# MAT_CABLING_CONNECTOR.net
KiCad netlist of a schematic drawn in Altium Designer
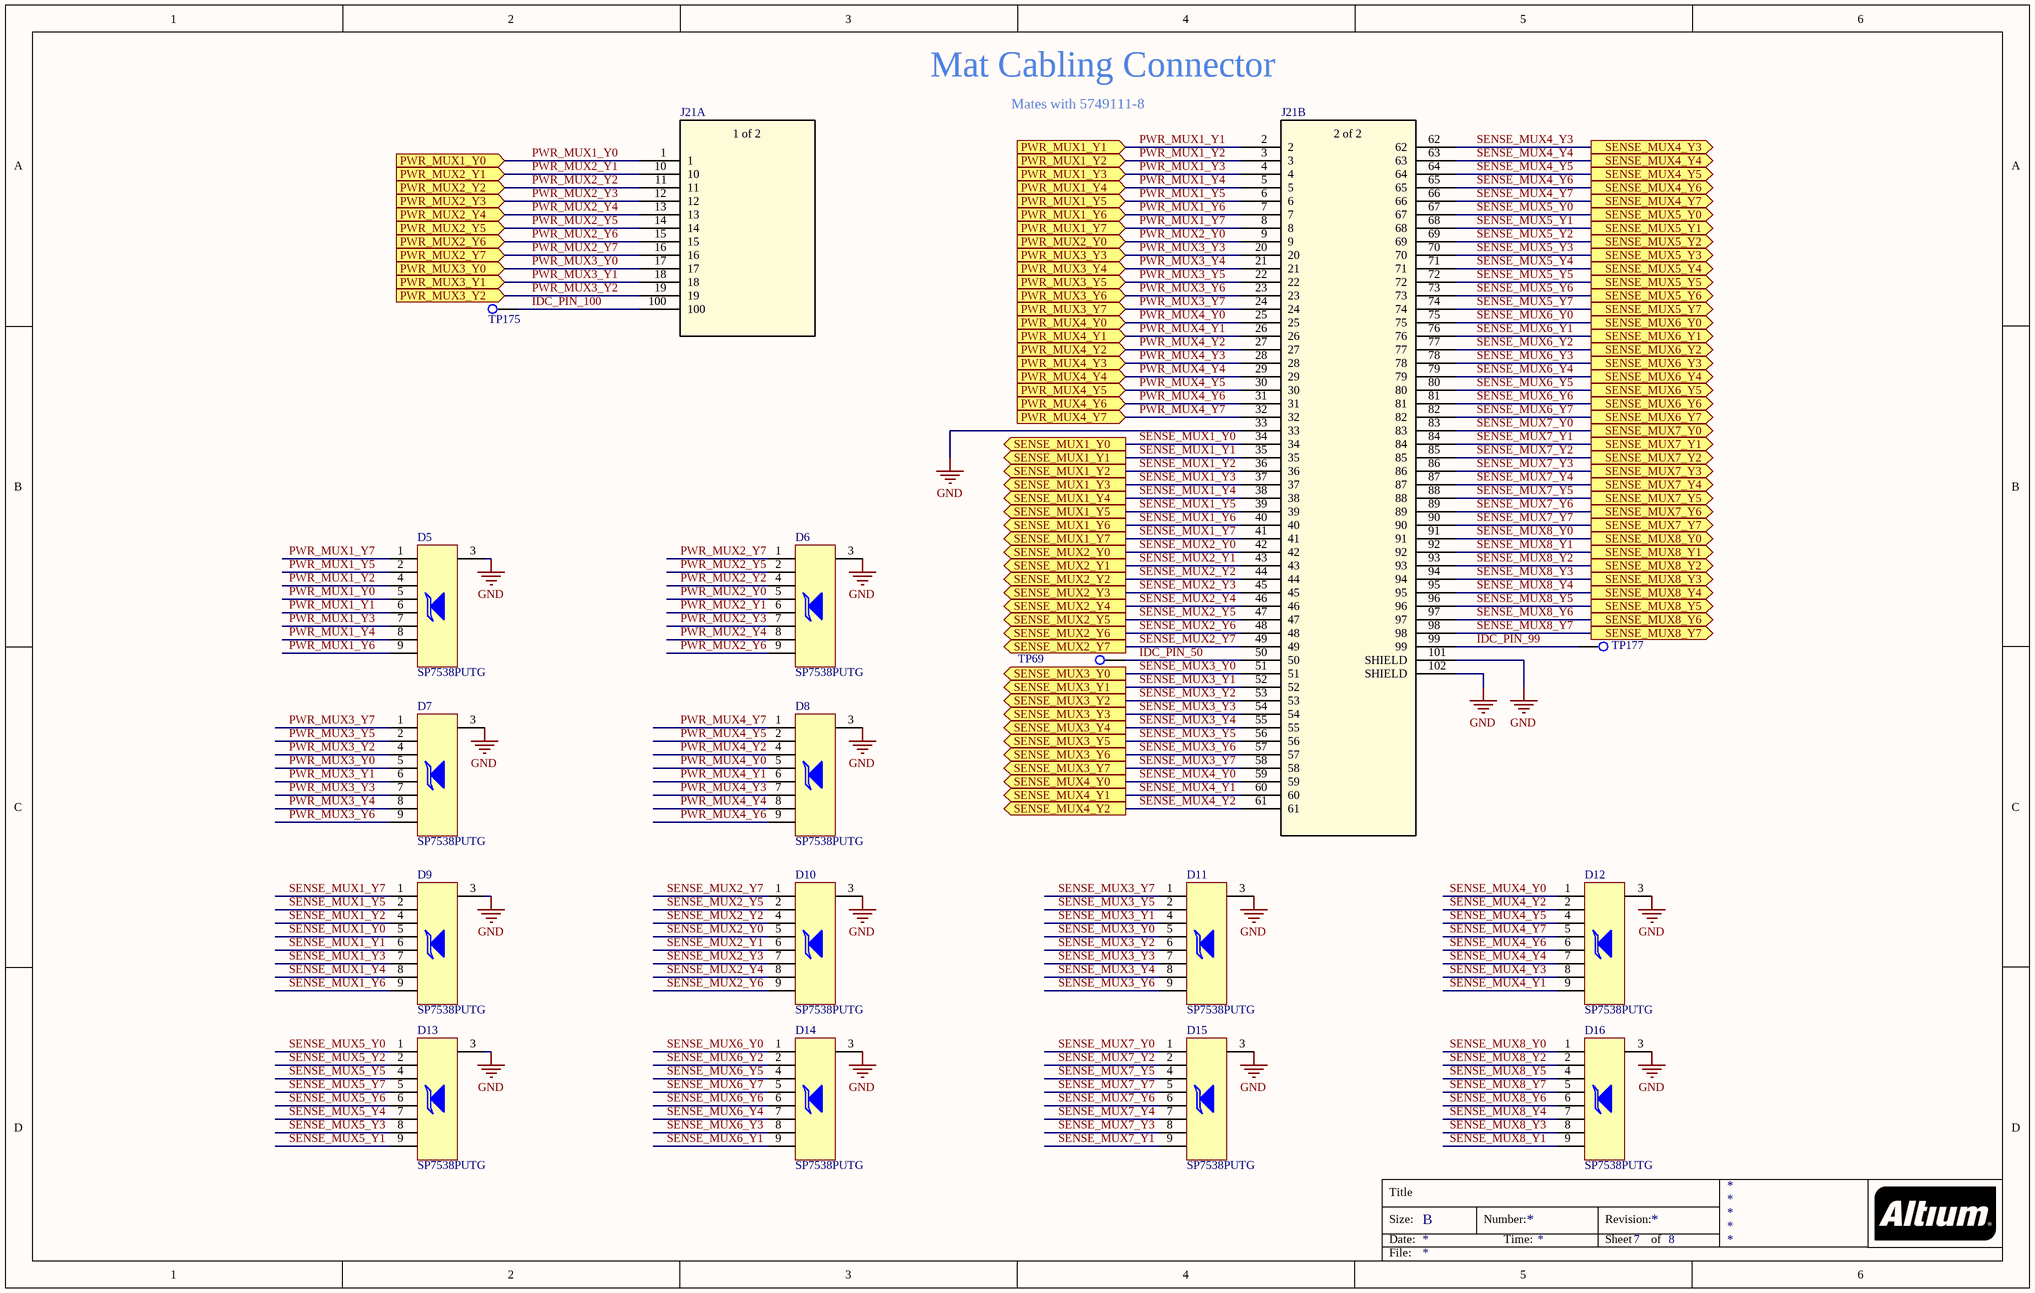
[diagram p0: MAT_CABLING_CONNECTOR.SchDoc]

(export (version "E")
  (design (tool "Eeschema 10.0.6"))
  (components
    (comp (ref "D5")
      (value "SP7538PUTG")
      (footprint "SP7538PUTG")
      (description "ESD Suppressor TVS Octal Uni-Dir 25kV 9-Pin UDFN T/R")
      (fields
        (field (name "MANUFACTURER") "Littelfuse")
        (field (name "MANUFACTURER PART NUMBER") "SP7538PUTG")
      )
      (libsource (lib "MLBSchLib") (part "SP7538PUTG"))
    )
    (comp (ref "D6")
      (value "SP7538PUTG")
      (footprint "SP7538PUTG")
      (description "ESD Suppressor TVS Octal Uni-Dir 25kV 9-Pin UDFN T/R")
      (fields
        (field (name "MANUFACTURER") "Littelfuse")
        (field (name "MANUFACTURER PART NUMBER") "SP7538PUTG")
      )
      (libsource (lib "MLBSchLib") (part "SP7538PUTG"))
    )
    (comp (ref "D7")
      (value "SP7538PUTG")
      (footprint "SP7538PUTG")
      (description "ESD Suppressor TVS Octal Uni-Dir 25kV 9-Pin UDFN T/R")
      (fields
        (field (name "MANUFACTURER") "Littelfuse")
        (field (name "MANUFACTURER PART NUMBER") "SP7538PUTG")
      )
      (libsource (lib "MLBSchLib") (part "SP7538PUTG"))
    )
    (comp (ref "D8")
      (value "SP7538PUTG")
      (footprint "SP7538PUTG")
      (description "ESD Suppressor TVS Octal Uni-Dir 25kV 9-Pin UDFN T/R")
      (fields
        (field (name "MANUFACTURER") "Littelfuse")
        (field (name "MANUFACTURER PART NUMBER") "SP7538PUTG")
      )
      (libsource (lib "MLBSchLib") (part "SP7538PUTG"))
    )
    (comp (ref "D9")
      (value "SP7538PUTG")
      (footprint "SP7538PUTG")
      (description "ESD Suppressor TVS Octal Uni-Dir 25kV 9-Pin UDFN T/R")
      (fields
        (field (name "MANUFACTURER") "Littelfuse")
        (field (name "MANUFACTURER PART NUMBER") "SP7538PUTG")
      )
      (libsource (lib "MLBSchLib") (part "SP7538PUTG"))
    )
    (comp (ref "D10")
      (value "SP7538PUTG")
      (footprint "SP7538PUTG")
      (description "ESD Suppressor TVS Octal Uni-Dir 25kV 9-Pin UDFN T/R")
      (fields
        (field (name "MANUFACTURER") "Littelfuse")
        (field (name "MANUFACTURER PART NUMBER") "SP7538PUTG")
      )
      (libsource (lib "MLBSchLib") (part "SP7538PUTG"))
    )
    (comp (ref "D11")
      (value "SP7538PUTG")
      (footprint "SP7538PUTG")
      (description "ESD Suppressor TVS Octal Uni-Dir 25kV 9-Pin UDFN T/R")
      (fields
        (field (name "MANUFACTURER") "Littelfuse")
        (field (name "MANUFACTURER PART NUMBER") "SP7538PUTG")
      )
      (libsource (lib "MLBSchLib") (part "SP7538PUTG"))
    )
    (comp (ref "D12")
      (value "SP7538PUTG")
      (footprint "SP7538PUTG")
      (description "ESD Suppressor TVS Octal Uni-Dir 25kV 9-Pin UDFN T/R")
      (fields
        (field (name "MANUFACTURER") "Littelfuse")
        (field (name "MANUFACTURER PART NUMBER") "SP7538PUTG")
      )
      (libsource (lib "MLBSchLib") (part "SP7538PUTG"))
    )
    (comp (ref "D13")
      (value "SP7538PUTG")
      (footprint "SP7538PUTG")
      (description "ESD Suppressor TVS Octal Uni-Dir 25kV 9-Pin UDFN T/R")
      (fields
        (field (name "MANUFACTURER") "Littelfuse")
        (field (name "MANUFACTURER PART NUMBER") "SP7538PUTG")
      )
      (libsource (lib "MLBSchLib") (part "SP7538PUTG"))
    )
    (comp (ref "D14")
      (value "SP7538PUTG")
      (footprint "SP7538PUTG")
      (description "ESD Suppressor TVS Octal Uni-Dir 25kV 9-Pin UDFN T/R")
      (fields
        (field (name "MANUFACTURER") "Littelfuse")
        (field (name "MANUFACTURER PART NUMBER") "SP7538PUTG")
      )
      (libsource (lib "MLBSchLib") (part "SP7538PUTG"))
    )
    (comp (ref "D15")
      (value "SP7538PUTG")
      (footprint "SP7538PUTG")
      (description "ESD Suppressor TVS Octal Uni-Dir 25kV 9-Pin UDFN T/R")
      (fields
        (field (name "MANUFACTURER") "Littelfuse")
        (field (name "MANUFACTURER PART NUMBER") "SP7538PUTG")
      )
      (libsource (lib "MLBSchLib") (part "SP7538PUTG"))
    )
    (comp (ref "D16")
      (value "SP7538PUTG")
      (footprint "SP7538PUTG")
      (description "ESD Suppressor TVS Octal Uni-Dir 25kV 9-Pin UDFN T/R")
      (fields
        (field (name "MANUFACTURER") "Littelfuse")
        (field (name "MANUFACTURER PART NUMBER") "SP7538PUTG")
      )
      (libsource (lib "MLBSchLib") (part "SP7538PUTG"))
    )
    (comp (ref "J21")
      (value "1-787082-8")
      (footprint "CONN100_1-787082-8_TEC")
      (description "No Description Available")
      (fields
        (field (name "MANUFACTURER") "TE Connectivity AMP Connectors")
        (field (name "COPYRIGHT") "Copyright (C) 2022 Ultra Librarian. All rights reserved.")
      )
      (libsource (lib "") (part "1-787082-8_1"))
    )
    (comp (ref "TP69")
      (value "RCU-0C")
      (footprint "TP+195X110")
      (description "Natural PC Test Point , Plating Surface Mount Mounting Type")
      (fields (field (name "MANUFACTURER") "TE Connectivity AMP Connectors"))
      (libsource (lib "MLBSchLib") (part "RCU-0C"))
    )
    (comp (ref "TP175")
      (value "RCU-0C")
      (footprint "TP+195X110")
      (description "Natural PC Test Point , Plating Surface Mount Mounting Type")
      (fields (field (name "MANUFACTURER") "TE Connectivity AMP Connectors"))
      (libsource (lib "MLBSchLib") (part "RCU-0C"))
    )
    (comp (ref "TP177")
      (value "RCU-0C")
      (footprint "TP+195X110")
      (description "Natural PC Test Point , Plating Surface Mount Mounting Type")
      (fields (field (name "MANUFACTURER") "TE Connectivity AMP Connectors"))
      (libsource (lib "MLBSchLib") (part "RCU-0C"))
    )
  )
  (nets
    (net (code "1") (name "/IDC_PIN_50") (class "Default")
      (node (ref "J21") (pin "50") (pinfunction "50_50") (pintype "passive"))
      (node (ref "TP69") (pin "1") (pinfunction "1_1") (pintype "passive"))
    )
    (net (code "2") (name "/IDC_PIN_99") (class "Default")
      (node (ref "J21") (pin "99") (pinfunction "99_99") (pintype "passive"))
      (node (ref "TP177") (pin "1") (pinfunction "1_1") (pintype "passive"))
    )
    (net (code "3") (name "/IDC_PIN_100") (class "Default")
      (node (ref "J21") (pin "100") (pinfunction "100_100") (pintype "passive"))
      (node (ref "TP175") (pin "1") (pinfunction "1_1") (pintype "passive"))
    )
    (net (code "4") (name "/PWR_MUX1_Y0") (class "Default")
      (node (ref "D5") (pin "5") (pinfunction "5_5") (pintype "passive"))
      (node (ref "J21") (pin "1") (pinfunction "1_1") (pintype "passive"))
    )
    (net (code "5") (name "/PWR_MUX1_Y1") (class "Default")
      (node (ref "D5") (pin "6") (pinfunction "6_6") (pintype "passive"))
      (node (ref "J21") (pin "2") (pinfunction "2_2") (pintype "passive"))
    )
    (net (code "6") (name "/PWR_MUX1_Y2") (class "Default")
      (node (ref "D5") (pin "4") (pinfunction "4_4") (pintype "passive"))
      (node (ref "J21") (pin "3") (pinfunction "3_3") (pintype "passive"))
    )
    (net (code "7") (name "/PWR_MUX1_Y3") (class "Default")
      (node (ref "D5") (pin "7") (pinfunction "7_7") (pintype "passive"))
      (node (ref "J21") (pin "4") (pinfunction "4_4") (pintype "passive"))
    )
    (net (code "8") (name "/PWR_MUX1_Y4") (class "Default")
      (node (ref "D5") (pin "8") (pinfunction "8_8") (pintype "passive"))
      (node (ref "J21") (pin "5") (pinfunction "5_5") (pintype "passive"))
    )
    (net (code "9") (name "/PWR_MUX1_Y5") (class "Default")
      (node (ref "D5") (pin "2") (pinfunction "2_2") (pintype "passive"))
      (node (ref "J21") (pin "6") (pinfunction "6_6") (pintype "passive"))
    )
    (net (code "10") (name "/PWR_MUX1_Y6") (class "Default")
      (node (ref "D5") (pin "9") (pinfunction "9_9") (pintype "passive"))
      (node (ref "J21") (pin "7") (pinfunction "7_7") (pintype "passive"))
    )
    (net (code "11") (name "/PWR_MUX1_Y7") (class "Default")
      (node (ref "D5") (pin "1") (pinfunction "1_1") (pintype "passive"))
      (node (ref "J21") (pin "8") (pinfunction "8_8") (pintype "passive"))
    )
    (net (code "12") (name "/PWR_MUX2_Y0") (class "Default")
      (node (ref "D6") (pin "5") (pinfunction "5_5") (pintype "passive"))
      (node (ref "J21") (pin "9") (pinfunction "9_9") (pintype "passive"))
    )
    (net (code "13") (name "/PWR_MUX2_Y1") (class "Default")
      (node (ref "D6") (pin "6") (pinfunction "6_6") (pintype "passive"))
      (node (ref "J21") (pin "10") (pinfunction "10_10") (pintype "passive"))
    )
    (net (code "14") (name "/PWR_MUX2_Y2") (class "Default")
      (node (ref "D6") (pin "4") (pinfunction "4_4") (pintype "passive"))
      (node (ref "J21") (pin "11") (pinfunction "11_11") (pintype "passive"))
    )
    (net (code "15") (name "/PWR_MUX2_Y3") (class "Default")
      (node (ref "D6") (pin "7") (pinfunction "7_7") (pintype "passive"))
      (node (ref "J21") (pin "12") (pinfunction "12_12") (pintype "passive"))
    )
    (net (code "16") (name "/PWR_MUX2_Y4") (class "Default")
      (node (ref "D6") (pin "8") (pinfunction "8_8") (pintype "passive"))
      (node (ref "J21") (pin "13") (pinfunction "13_13") (pintype "passive"))
    )
    (net (code "17") (name "/PWR_MUX2_Y5") (class "Default")
      (node (ref "D6") (pin "2") (pinfunction "2_2") (pintype "passive"))
      (node (ref "J21") (pin "14") (pinfunction "14_14") (pintype "passive"))
    )
    (net (code "18") (name "/PWR_MUX2_Y6") (class "Default")
      (node (ref "D6") (pin "9") (pinfunction "9_9") (pintype "passive"))
      (node (ref "J21") (pin "15") (pinfunction "15_15") (pintype "passive"))
    )
    (net (code "19") (name "/PWR_MUX2_Y7") (class "Default")
      (node (ref "D6") (pin "1") (pinfunction "1_1") (pintype "passive"))
      (node (ref "J21") (pin "16") (pinfunction "16_16") (pintype "passive"))
    )
    (net (code "20") (name "/PWR_MUX3_Y0") (class "Default")
      (node (ref "D7") (pin "5") (pinfunction "5_5") (pintype "passive"))
      (node (ref "J21") (pin "17") (pinfunction "17_17") (pintype "passive"))
    )
    (net (code "21") (name "/PWR_MUX3_Y1") (class "Default")
      (node (ref "D7") (pin "6") (pinfunction "6_6") (pintype "passive"))
      (node (ref "J21") (pin "18") (pinfunction "18_18") (pintype "passive"))
    )
    (net (code "22") (name "/PWR_MUX3_Y2") (class "Default")
      (node (ref "D7") (pin "4") (pinfunction "4_4") (pintype "passive"))
      (node (ref "J21") (pin "19") (pinfunction "19_19") (pintype "passive"))
    )
    (net (code "23") (name "/PWR_MUX3_Y3") (class "Default")
      (node (ref "D7") (pin "7") (pinfunction "7_7") (pintype "passive"))
      (node (ref "J21") (pin "20") (pinfunction "20_20") (pintype "passive"))
    )
    (net (code "24") (name "/PWR_MUX3_Y4") (class "Default")
      (node (ref "D7") (pin "8") (pinfunction "8_8") (pintype "passive"))
      (node (ref "J21") (pin "21") (pinfunction "21_21") (pintype "passive"))
    )
    (net (code "25") (name "/PWR_MUX3_Y5") (class "Default")
      (node (ref "D7") (pin "2") (pinfunction "2_2") (pintype "passive"))
      (node (ref "J21") (pin "22") (pinfunction "22_22") (pintype "passive"))
    )
    (net (code "26") (name "/PWR_MUX3_Y6") (class "Default")
      (node (ref "D7") (pin "9") (pinfunction "9_9") (pintype "passive"))
      (node (ref "J21") (pin "23") (pinfunction "23_23") (pintype "passive"))
    )
    (net (code "27") (name "/PWR_MUX3_Y7") (class "Default")
      (node (ref "D7") (pin "1") (pinfunction "1_1") (pintype "passive"))
      (node (ref "J21") (pin "24") (pinfunction "24_24") (pintype "passive"))
    )
    (net (code "28") (name "/PWR_MUX4_Y0") (class "Default")
      (node (ref "D8") (pin "5") (pinfunction "5_5") (pintype "passive"))
      (node (ref "J21") (pin "25") (pinfunction "25_25") (pintype "passive"))
    )
    (net (code "29") (name "/PWR_MUX4_Y1") (class "Default")
      (node (ref "D8") (pin "6") (pinfunction "6_6") (pintype "passive"))
      (node (ref "J21") (pin "26") (pinfunction "26_26") (pintype "passive"))
    )
    (net (code "30") (name "/PWR_MUX4_Y2") (class "Default")
      (node (ref "D8") (pin "4") (pinfunction "4_4") (pintype "passive"))
      (node (ref "J21") (pin "27") (pinfunction "27_27") (pintype "passive"))
    )
    (net (code "31") (name "/PWR_MUX4_Y3") (class "Default")
      (node (ref "D8") (pin "7") (pinfunction "7_7") (pintype "passive"))
      (node (ref "J21") (pin "28") (pinfunction "28_28") (pintype "passive"))
    )
    (net (code "32") (name "/PWR_MUX4_Y4") (class "Default")
      (node (ref "D8") (pin "8") (pinfunction "8_8") (pintype "passive"))
      (node (ref "J21") (pin "29") (pinfunction "29_29") (pintype "passive"))
    )
    (net (code "33") (name "/PWR_MUX4_Y5") (class "Default")
      (node (ref "D8") (pin "2") (pinfunction "2_2") (pintype "passive"))
      (node (ref "J21") (pin "30") (pinfunction "30_30") (pintype "passive"))
    )
    (net (code "34") (name "/PWR_MUX4_Y6") (class "Default")
      (node (ref "D8") (pin "9") (pinfunction "9_9") (pintype "passive"))
      (node (ref "J21") (pin "31") (pinfunction "31_31") (pintype "passive"))
    )
    (net (code "35") (name "/PWR_MUX4_Y7") (class "Default")
      (node (ref "D8") (pin "1") (pinfunction "1_1") (pintype "passive"))
      (node (ref "J21") (pin "32") (pinfunction "32_32") (pintype "passive"))
    )
    (net (code "36") (name "/SENSE_MUX1_Y0") (class "Default")
      (node (ref "D9") (pin "5") (pinfunction "5_5") (pintype "passive"))
      (node (ref "J21") (pin "34") (pinfunction "34_34") (pintype "passive"))
    )
    (net (code "37") (name "/SENSE_MUX1_Y1") (class "Default")
      (node (ref "D9") (pin "6") (pinfunction "6_6") (pintype "passive"))
      (node (ref "J21") (pin "35") (pinfunction "35_35") (pintype "passive"))
    )
    (net (code "38") (name "/SENSE_MUX1_Y2") (class "Default")
      (node (ref "D9") (pin "4") (pinfunction "4_4") (pintype "passive"))
      (node (ref "J21") (pin "36") (pinfunction "36_36") (pintype "passive"))
    )
    (net (code "39") (name "/SENSE_MUX1_Y3") (class "Default")
      (node (ref "D9") (pin "7") (pinfunction "7_7") (pintype "passive"))
      (node (ref "J21") (pin "37") (pinfunction "37_37") (pintype "passive"))
    )
    (net (code "40") (name "/SENSE_MUX1_Y4") (class "Default")
      (node (ref "D9") (pin "8") (pinfunction "8_8") (pintype "passive"))
      (node (ref "J21") (pin "38") (pinfunction "38_38") (pintype "passive"))
    )
    (net (code "41") (name "/SENSE_MUX1_Y5") (class "Default")
      (node (ref "D9") (pin "2") (pinfunction "2_2") (pintype "passive"))
      (node (ref "J21") (pin "39") (pinfunction "39_39") (pintype "passive"))
    )
    (net (code "42") (name "/SENSE_MUX1_Y6") (class "Default")
      (node (ref "D9") (pin "9") (pinfunction "9_9") (pintype "passive"))
      (node (ref "J21") (pin "40") (pinfunction "40_40") (pintype "passive"))
    )
    (net (code "43") (name "/SENSE_MUX1_Y7") (class "Default")
      (node (ref "D9") (pin "1") (pinfunction "1_1") (pintype "passive"))
      (node (ref "J21") (pin "41") (pinfunction "41_41") (pintype "passive"))
    )
    (net (code "44") (name "/SENSE_MUX2_Y0") (class "Default")
      (node (ref "D10") (pin "5") (pinfunction "5_5") (pintype "passive"))
      (node (ref "J21") (pin "42") (pinfunction "42_42") (pintype "passive"))
    )
    (net (code "45") (name "/SENSE_MUX2_Y1") (class "Default")
      (node (ref "D10") (pin "6") (pinfunction "6_6") (pintype "passive"))
      (node (ref "J21") (pin "43") (pinfunction "43_43") (pintype "passive"))
    )
    (net (code "46") (name "/SENSE_MUX2_Y2") (class "Default")
      (node (ref "D10") (pin "4") (pinfunction "4_4") (pintype "passive"))
      (node (ref "J21") (pin "44") (pinfunction "44_44") (pintype "passive"))
    )
    (net (code "47") (name "/SENSE_MUX2_Y3") (class "Default")
      (node (ref "D10") (pin "7") (pinfunction "7_7") (pintype "passive"))
      (node (ref "J21") (pin "45") (pinfunction "45_45") (pintype "passive"))
    )
    (net (code "48") (name "/SENSE_MUX2_Y4") (class "Default")
      (node (ref "D10") (pin "8") (pinfunction "8_8") (pintype "passive"))
      (node (ref "J21") (pin "46") (pinfunction "46_46") (pintype "passive"))
    )
    (net (code "49") (name "/SENSE_MUX2_Y5") (class "Default")
      (node (ref "D10") (pin "2") (pinfunction "2_2") (pintype "passive"))
      (node (ref "J21") (pin "47") (pinfunction "47_47") (pintype "passive"))
    )
    (net (code "50") (name "/SENSE_MUX2_Y6") (class "Default")
      (node (ref "D10") (pin "9") (pinfunction "9_9") (pintype "passive"))
      (node (ref "J21") (pin "48") (pinfunction "48_48") (pintype "passive"))
    )
    (net (code "51") (name "/SENSE_MUX2_Y7") (class "Default")
      (node (ref "D10") (pin "1") (pinfunction "1_1") (pintype "passive"))
      (node (ref "J21") (pin "49") (pinfunction "49_49") (pintype "passive"))
    )
    (net (code "52") (name "/SENSE_MUX3_Y0") (class "Default")
      (node (ref "D11") (pin "5") (pinfunction "5_5") (pintype "passive"))
      (node (ref "J21") (pin "51") (pinfunction "51_51") (pintype "passive"))
    )
    (net (code "53") (name "/SENSE_MUX3_Y1") (class "Default")
      (node (ref "D11") (pin "4") (pinfunction "4_4") (pintype "passive"))
      (node (ref "J21") (pin "52") (pinfunction "52_52") (pintype "passive"))
    )
    (net (code "54") (name "/SENSE_MUX3_Y2") (class "Default")
      (node (ref "D11") (pin "6") (pinfunction "6_6") (pintype "passive"))
      (node (ref "J21") (pin "53") (pinfunction "53_53") (pintype "passive"))
    )
    (net (code "55") (name "/SENSE_MUX3_Y3") (class "Default")
      (node (ref "D11") (pin "7") (pinfunction "7_7") (pintype "passive"))
      (node (ref "J21") (pin "54") (pinfunction "54_54") (pintype "passive"))
    )
    (net (code "56") (name "/SENSE_MUX3_Y4") (class "Default")
      (node (ref "D11") (pin "8") (pinfunction "8_8") (pintype "passive"))
      (node (ref "J21") (pin "55") (pinfunction "55_55") (pintype "passive"))
    )
    (net (code "57") (name "/SENSE_MUX3_Y5") (class "Default")
      (node (ref "D11") (pin "2") (pinfunction "2_2") (pintype "passive"))
      (node (ref "J21") (pin "56") (pinfunction "56_56") (pintype "passive"))
    )
    (net (code "58") (name "/SENSE_MUX3_Y6") (class "Default")
      (node (ref "D11") (pin "9") (pinfunction "9_9") (pintype "passive"))
      (node (ref "J21") (pin "57") (pinfunction "57_57") (pintype "passive"))
    )
    (net (code "59") (name "/SENSE_MUX3_Y7") (class "Default")
      (node (ref "D11") (pin "1") (pinfunction "1_1") (pintype "passive"))
      (node (ref "J21") (pin "58") (pinfunction "58_58") (pintype "passive"))
    )
    (net (code "60") (name "/SENSE_MUX4_Y0") (class "Default")
      (node (ref "D12") (pin "1") (pinfunction "1_1") (pintype "passive"))
      (node (ref "J21") (pin "59") (pinfunction "59_59") (pintype "passive"))
    )
    (net (code "61") (name "/SENSE_MUX4_Y1") (class "Default")
      (node (ref "D12") (pin "9") (pinfunction "9_9") (pintype "passive"))
      (node (ref "J21") (pin "60") (pinfunction "60_60") (pintype "passive"))
    )
    (net (code "62") (name "/SENSE_MUX4_Y2") (class "Default")
      (node (ref "D12") (pin "2") (pinfunction "2_2") (pintype "passive"))
      (node (ref "J21") (pin "61") (pinfunction "61_61") (pintype "passive"))
    )
    (net (code "63") (name "/SENSE_MUX4_Y3") (class "Default")
      (node (ref "D12") (pin "8") (pinfunction "8_8") (pintype "passive"))
      (node (ref "J21") (pin "62") (pinfunction "62_62") (pintype "passive"))
    )
    (net (code "64") (name "/SENSE_MUX4_Y4") (class "Default")
      (node (ref "D12") (pin "7") (pinfunction "7_7") (pintype "passive"))
      (node (ref "J21") (pin "63") (pinfunction "63_63") (pintype "passive"))
    )
    (net (code "65") (name "/SENSE_MUX4_Y5") (class "Default")
      (node (ref "D12") (pin "4") (pinfunction "4_4") (pintype "passive"))
      (node (ref "J21") (pin "64") (pinfunction "64_64") (pintype "passive"))
    )
    (net (code "66") (name "/SENSE_MUX4_Y6") (class "Default")
      (node (ref "D12") (pin "6") (pinfunction "6_6") (pintype "passive"))
      (node (ref "J21") (pin "65") (pinfunction "65_65") (pintype "passive"))
    )
    (net (code "67") (name "/SENSE_MUX4_Y7") (class "Default")
      (node (ref "D12") (pin "5") (pinfunction "5_5") (pintype "passive"))
      (node (ref "J21") (pin "66") (pinfunction "66_66") (pintype "passive"))
    )
    (net (code "68") (name "/SENSE_MUX5_Y0") (class "Default")
      (node (ref "D13") (pin "1") (pinfunction "1_1") (pintype "passive"))
      (node (ref "J21") (pin "67") (pinfunction "67_67") (pintype "passive"))
    )
    (net (code "69") (name "/SENSE_MUX5_Y1") (class "Default")
      (node (ref "D13") (pin "9") (pinfunction "9_9") (pintype "passive"))
      (node (ref "J21") (pin "68") (pinfunction "68_68") (pintype "passive"))
    )
    (net (code "70") (name "/SENSE_MUX5_Y2") (class "Default")
      (node (ref "D13") (pin "2") (pinfunction "2_2") (pintype "passive"))
      (node (ref "J21") (pin "69") (pinfunction "69_69") (pintype "passive"))
    )
    (net (code "71") (name "/SENSE_MUX5_Y3") (class "Default")
      (node (ref "D13") (pin "8") (pinfunction "8_8") (pintype "passive"))
      (node (ref "J21") (pin "70") (pinfunction "70_70") (pintype "passive"))
    )
    (net (code "72") (name "/SENSE_MUX5_Y4") (class "Default")
      (node (ref "D13") (pin "7") (pinfunction "7_7") (pintype "passive"))
      (node (ref "J21") (pin "71") (pinfunction "71_71") (pintype "passive"))
    )
    (net (code "73") (name "/SENSE_MUX5_Y5") (class "Default")
      (node (ref "D13") (pin "4") (pinfunction "4_4") (pintype "passive"))
      (node (ref "J21") (pin "72") (pinfunction "72_72") (pintype "passive"))
    )
    (net (code "74") (name "/SENSE_MUX5_Y6") (class "Default")
      (node (ref "D13") (pin "6") (pinfunction "6_6") (pintype "passive"))
      (node (ref "J21") (pin "73") (pinfunction "73_73") (pintype "passive"))
    )
    (net (code "75") (name "/SENSE_MUX5_Y7") (class "Default")
      (node (ref "D13") (pin "5") (pinfunction "5_5") (pintype "passive"))
      (node (ref "J21") (pin "74") (pinfunction "74_74") (pintype "passive"))
    )
    (net (code "76") (name "/SENSE_MUX6_Y0") (class "Default")
      (node (ref "D14") (pin "1") (pinfunction "1_1") (pintype "passive"))
      (node (ref "J21") (pin "75") (pinfunction "75_75") (pintype "passive"))
    )
    (net (code "77") (name "/SENSE_MUX6_Y1") (class "Default")
      (node (ref "D14") (pin "9") (pinfunction "9_9") (pintype "passive"))
      (node (ref "J21") (pin "76") (pinfunction "76_76") (pintype "passive"))
    )
    (net (code "78") (name "/SENSE_MUX6_Y2") (class "Default")
      (node (ref "D14") (pin "2") (pinfunction "2_2") (pintype "passive"))
      (node (ref "J21") (pin "77") (pinfunction "77_77") (pintype "passive"))
    )
    (net (code "79") (name "/SENSE_MUX6_Y3") (class "Default")
      (node (ref "D14") (pin "8") (pinfunction "8_8") (pintype "passive"))
      (node (ref "J21") (pin "78") (pinfunction "78_78") (pintype "passive"))
    )
    (net (code "80") (name "/SENSE_MUX6_Y4") (class "Default")
      (node (ref "D14") (pin "7") (pinfunction "7_7") (pintype "passive"))
      (node (ref "J21") (pin "79") (pinfunction "79_79") (pintype "passive"))
    )
    (net (code "81") (name "/SENSE_MUX6_Y5") (class "Default")
      (node (ref "D14") (pin "4") (pinfunction "4_4") (pintype "passive"))
      (node (ref "J21") (pin "80") (pinfunction "80_80") (pintype "passive"))
    )
    (net (code "82") (name "/SENSE_MUX6_Y6") (class "Default")
      (node (ref "D14") (pin "6") (pinfunction "6_6") (pintype "passive"))
      (node (ref "J21") (pin "81") (pinfunction "81_81") (pintype "passive"))
    )
    (net (code "83") (name "/SENSE_MUX6_Y7") (class "Default")
      (node (ref "D14") (pin "5") (pinfunction "5_5") (pintype "passive"))
      (node (ref "J21") (pin "82") (pinfunction "82_82") (pintype "passive"))
    )
    (net (code "84") (name "/SENSE_MUX7_Y0") (class "Default")
      (node (ref "D15") (pin "1") (pinfunction "1_1") (pintype "passive"))
      (node (ref "J21") (pin "83") (pinfunction "83_83") (pintype "passive"))
    )
    (net (code "85") (name "/SENSE_MUX7_Y1") (class "Default")
      (node (ref "D15") (pin "9") (pinfunction "9_9") (pintype "passive"))
      (node (ref "J21") (pin "84") (pinfunction "84_84") (pintype "passive"))
    )
    (net (code "86") (name "/SENSE_MUX7_Y2") (class "Default")
      (node (ref "D15") (pin "2") (pinfunction "2_2") (pintype "passive"))
      (node (ref "J21") (pin "85") (pinfunction "85_85") (pintype "passive"))
    )
    (net (code "87") (name "/SENSE_MUX7_Y3") (class "Default")
      (node (ref "D15") (pin "8") (pinfunction "8_8") (pintype "passive"))
      (node (ref "J21") (pin "86") (pinfunction "86_86") (pintype "passive"))
    )
    (net (code "88") (name "/SENSE_MUX7_Y4") (class "Default")
      (node (ref "D15") (pin "7") (pinfunction "7_7") (pintype "passive"))
      (node (ref "J21") (pin "87") (pinfunction "87_87") (pintype "passive"))
    )
    (net (code "89") (name "/SENSE_MUX7_Y5") (class "Default")
      (node (ref "D15") (pin "4") (pinfunction "4_4") (pintype "passive"))
      (node (ref "J21") (pin "88") (pinfunction "88_88") (pintype "passive"))
    )
    (net (code "90") (name "/SENSE_MUX7_Y6") (class "Default")
      (node (ref "D15") (pin "6") (pinfunction "6_6") (pintype "passive"))
      (node (ref "J21") (pin "89") (pinfunction "89_89") (pintype "passive"))
    )
    (net (code "91") (name "/SENSE_MUX7_Y7") (class "Default")
      (node (ref "D15") (pin "5") (pinfunction "5_5") (pintype "passive"))
      (node (ref "J21") (pin "90") (pinfunction "90_90") (pintype "passive"))
    )
    (net (code "92") (name "/SENSE_MUX8_Y0") (class "Default")
      (node (ref "D16") (pin "1") (pinfunction "1_1") (pintype "passive"))
      (node (ref "J21") (pin "91") (pinfunction "91_91") (pintype "passive"))
    )
    (net (code "93") (name "/SENSE_MUX8_Y1") (class "Default")
      (node (ref "D16") (pin "9") (pinfunction "9_9") (pintype "passive"))
      (node (ref "J21") (pin "92") (pinfunction "92_92") (pintype "passive"))
    )
    (net (code "94") (name "/SENSE_MUX8_Y2") (class "Default")
      (node (ref "D16") (pin "2") (pinfunction "2_2") (pintype "passive"))
      (node (ref "J21") (pin "93") (pinfunction "93_93") (pintype "passive"))
    )
    (net (code "95") (name "/SENSE_MUX8_Y3") (class "Default")
      (node (ref "D16") (pin "8") (pinfunction "8_8") (pintype "passive"))
      (node (ref "J21") (pin "94") (pinfunction "94_94") (pintype "passive"))
    )
    (net (code "96") (name "/SENSE_MUX8_Y4") (class "Default")
      (node (ref "D16") (pin "7") (pinfunction "7_7") (pintype "passive"))
      (node (ref "J21") (pin "95") (pinfunction "95_95") (pintype "passive"))
    )
    (net (code "97") (name "/SENSE_MUX8_Y5") (class "Default")
      (node (ref "D16") (pin "4") (pinfunction "4_4") (pintype "passive"))
      (node (ref "J21") (pin "96") (pinfunction "96_96") (pintype "passive"))
    )
    (net (code "98") (name "/SENSE_MUX8_Y6") (class "Default")
      (node (ref "D16") (pin "6") (pinfunction "6_6") (pintype "passive"))
      (node (ref "J21") (pin "97") (pinfunction "97_97") (pintype "passive"))
    )
    (net (code "99") (name "/SENSE_MUX8_Y7") (class "Default")
      (node (ref "D16") (pin "5") (pinfunction "5_5") (pintype "passive"))
      (node (ref "J21") (pin "98") (pinfunction "98_98") (pintype "passive"))
    )
    (net (code "100") (name "GND") (class "Default")
      (node (ref "D10") (pin "3") (pinfunction "3_3") (pintype "passive"))
      (node (ref "D11") (pin "3") (pinfunction "3_3") (pintype "passive"))
      (node (ref "D12") (pin "3") (pinfunction "3_3") (pintype "passive"))
      (node (ref "D13") (pin "3") (pinfunction "3_3") (pintype "passive"))
      (node (ref "D14") (pin "3") (pinfunction "3_3") (pintype "passive"))
      (node (ref "D15") (pin "3") (pinfunction "3_3") (pintype "passive"))
      (node (ref "D16") (pin "3") (pinfunction "3_3") (pintype "passive"))
      (node (ref "D5") (pin "3") (pinfunction "3_3") (pintype "passive"))
      (node (ref "D6") (pin "3") (pinfunction "3_3") (pintype "passive"))
      (node (ref "D7") (pin "3") (pinfunction "3_3") (pintype "passive"))
      (node (ref "D8") (pin "3") (pinfunction "3_3") (pintype "passive"))
      (node (ref "D9") (pin "3") (pinfunction "3_3") (pintype "passive"))
      (node (ref "J21") (pin "101") (pinfunction "SHIELD_101") (pintype "passive"))
      (node (ref "J21") (pin "102") (pinfunction "SHIELD_102") (pintype "passive"))
      (node (ref "J21") (pin "33") (pinfunction "33_33") (pintype "passive"))
    )
  )
)
